# CD2840ADX-V2_1.net
KiCad netlist of a schematic drawn in Altium Designer
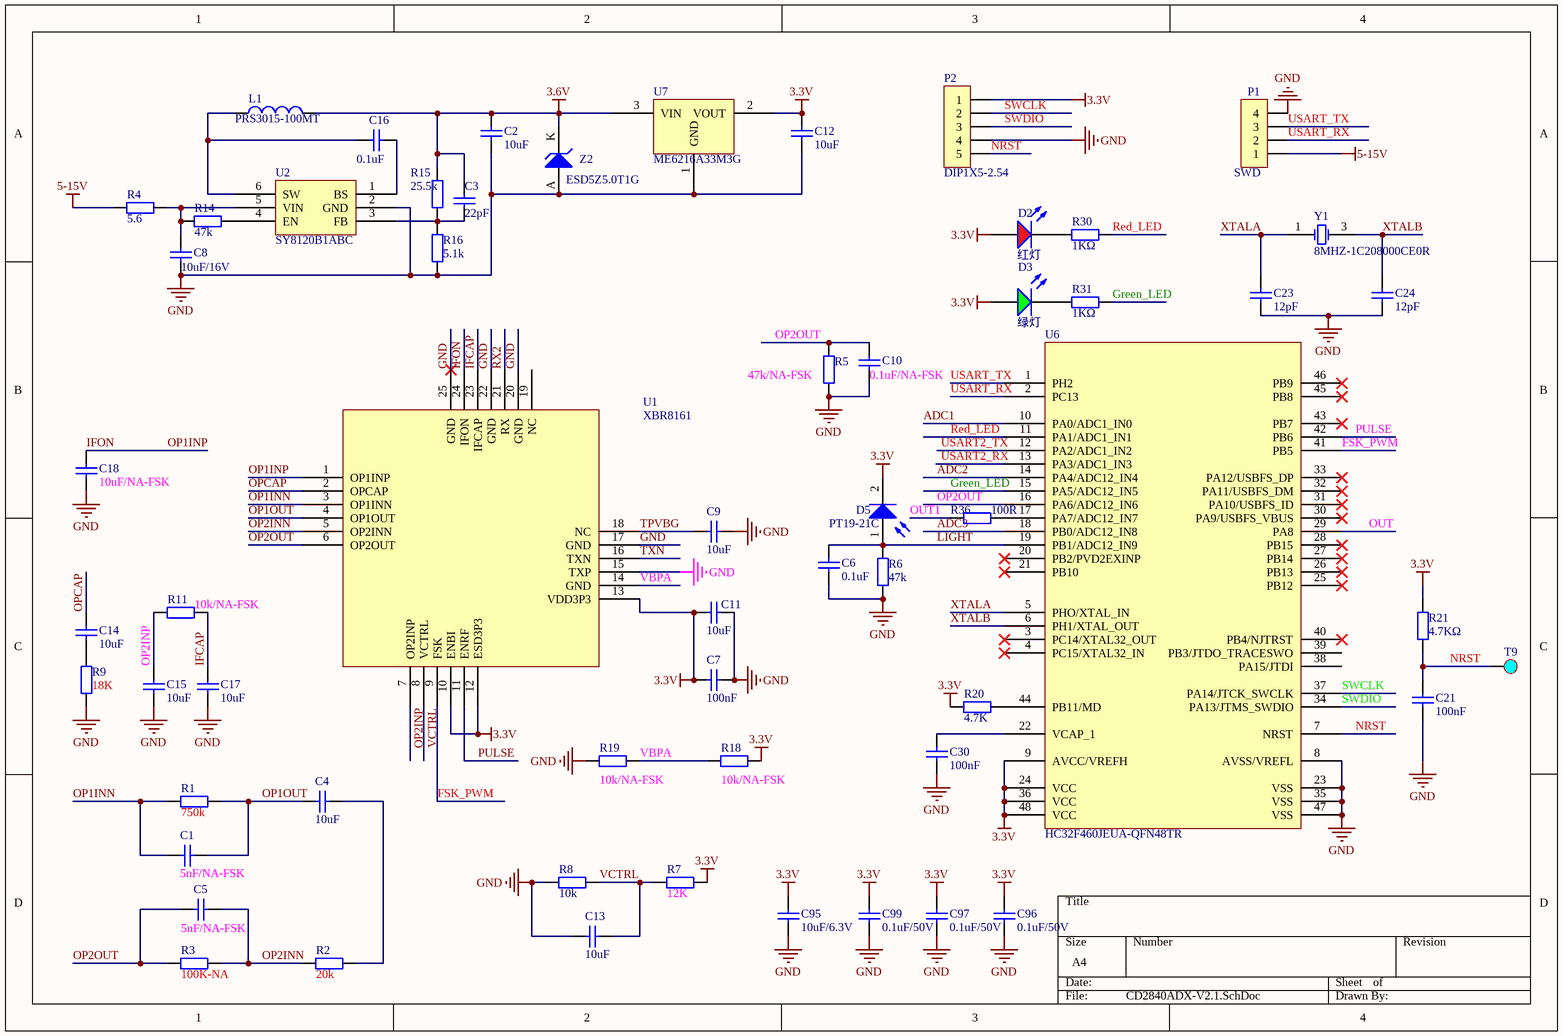
[diagram p0: CD2840ADX-V2.1.SchDoc]

(export (version "E")
  (design (tool "Eeschema 10.0.6"))
  (components
    (comp (ref "C1")
      (value "5nF/NA-FSK")
      (footprint "C0402")
      (description "Capacitor")
      (fields (field (name "PUBLISHER") "Altium Limited"))
      (libsource (lib "Miscellaneous Devices") (part "Cap"))
    )
    (comp (ref "C2")
      (value "10uF")
      (footprint "C0402")
      (description "Capacitor")
      (fields (field (name "PUBLISHER") "Altium Limited"))
      (libsource (lib "Miscellaneous Devices") (part "Cap"))
    )
    (comp (ref "C3")
      (value "22pF")
      (footprint "C0402")
      (description "Capacitor")
      (fields (field (name "PUBLISHER") "Altium Limited"))
      (libsource (lib "Miscellaneous Devices") (part "Cap"))
    )
    (comp (ref "C4")
      (value "10uF")
      (footprint "C0402")
      (description "Capacitor")
      (fields (field (name "PUBLISHER") "Altium Limited"))
      (libsource (lib "Miscellaneous Devices") (part "Cap"))
    )
    (comp (ref "C5")
      (value "5nF/NA-FSK")
      (footprint "C0402")
      (description "Capacitor")
      (fields (field (name "PUBLISHER") "Altium Limited"))
      (libsource (lib "Miscellaneous Devices") (part "Cap"))
    )
    (comp (ref "C6")
      (value "0.1uF")
      (footprint "C0402")
      (description "Capacitor")
      (fields (field (name "PUBLISHER") "Altium Limited"))
      (libsource (lib "Miscellaneous Devices") (part "Cap"))
    )
    (comp (ref "C7")
      (value "100nF")
      (footprint "C0402")
      (description "Capacitor")
      (fields (field (name "PUBLISHER") "Altium Limited"))
      (libsource (lib "Miscellaneous Devices") (part "Cap"))
    )
    (comp (ref "C8")
      (value "10uF/16V")
      (footprint "C0603")
      (description "Capacitor")
      (fields (field (name "PUBLISHER") "Altium Limited"))
      (libsource (lib "Miscellaneous Devices") (part "Cap"))
    )
    (comp (ref "C9")
      (value "10uF")
      (footprint "C0402")
      (description "Capacitor")
      (fields (field (name "PUBLISHER") "Altium Limited"))
      (libsource (lib "Miscellaneous Devices") (part "Cap"))
    )
    (comp (ref "C10")
      (value "0.1uF/NA-FSK")
      (footprint "C0402")
      (description "Capacitor")
      (fields (field (name "PUBLISHER") "Altium Limited"))
      (libsource (lib "Miscellaneous Devices") (part "Cap"))
    )
    (comp (ref "C11")
      (value "10uF")
      (footprint "C0402")
      (description "Capacitor")
      (fields (field (name "PUBLISHER") "Altium Limited"))
      (libsource (lib "Miscellaneous Devices") (part "Cap"))
    )
    (comp (ref "C12")
      (value "10uF")
      (footprint "C0402")
      (description "Capacitor")
      (fields (field (name "PUBLISHER") "Altium Limited"))
      (libsource (lib "Miscellaneous Devices") (part "Cap"))
    )
    (comp (ref "C13")
      (value "10uF")
      (footprint "C0402")
      (description "Capacitor")
      (fields (field (name "PUBLISHER") "Altium Limited"))
      (libsource (lib "Miscellaneous Devices") (part "Cap"))
    )
    (comp (ref "C14")
      (value "10uF")
      (footprint "C0402")
      (description "Capacitor")
      (fields (field (name "PUBLISHER") "Altium Limited"))
      (libsource (lib "Miscellaneous Devices") (part "Cap"))
    )
    (comp (ref "C15")
      (value "10uF")
      (footprint "C0402")
      (description "Capacitor")
      (fields (field (name "PUBLISHER") "Altium Limited"))
      (libsource (lib "Miscellaneous Devices") (part "Cap"))
    )
    (comp (ref "C16")
      (value "0.1uF")
      (footprint "C0402")
      (description "Capacitor")
      (fields (field (name "PUBLISHER") "Altium Limited"))
      (libsource (lib "Miscellaneous Devices") (part "Cap"))
    )
    (comp (ref "C17")
      (value "10uF")
      (footprint "C0402")
      (description "Capacitor")
      (fields (field (name "PUBLISHER") "Altium Limited"))
      (libsource (lib "Miscellaneous Devices") (part "Cap"))
    )
    (comp (ref "C18")
      (value "10uF/NA-FSK")
      (footprint "C0402")
      (description "Capacitor")
      (fields (field (name "PUBLISHER") "Altium Limited"))
      (libsource (lib "Miscellaneous Devices") (part "Cap"))
    )
    (comp (ref "C21")
      (value "100nF")
      (footprint "C0402")
      (description "贴片电容")
      (libsource (lib "Miscellaneous Devices LC") (part "0402 100nF (104) 10% 16V"))
    )
    (comp (ref "C23")
      (value "12pF")
      (footprint "C0402")
      (description "贴片电容")
      (libsource (lib "Cap") (part "0402 22pF (220) 5% 50V"))
    )
    (comp (ref "C24")
      (value "12pF")
      (footprint "C0402")
      (description "贴片电容")
      (libsource (lib "Cap") (part "0402 22pF (220) 5% 50V"))
    )
    (comp (ref "C30")
      (value "100nF")
      (footprint "C0402")
      (description "Capacitor")
      (fields (field (name "PUBLISHER") "Altium Limited"))
      (libsource (lib "Miscellaneous Devices") (part "Cap"))
    )
    (comp (ref "C95")
      (value "10uF/6.3V")
      (footprint "C0402")
      (description "贴片电容")
      (libsource (lib "Cap") (part "0402 2.2nF (222) 10% 50V"))
    )
    (comp (ref "C96")
      (value "0.1uF/50V")
      (footprint "C0402")
      (description "贴片电容")
      (libsource (lib "Cap") (part "0402 2.2nF (222) 10% 50V"))
    )
    (comp (ref "C97")
      (value "0.1uF/50V")
      (footprint "C0402")
      (description "贴片电容")
      (libsource (lib "Cap") (part "0402 2.2nF (222) 10% 50V"))
    )
    (comp (ref "C99")
      (value "0.1uF/50V")
      (footprint "C0402")
      (description "贴片电容")
      (libsource (lib "Cap") (part "0402 2.2nF (222) 10% 50V"))
    )
    (comp (ref "D2")
      (value "红灯")
      (footprint "LC-0603_LED_S1")
      (description "发光二极管")
      (libsource (lib "Miscellaneous Devices LC") (part "0603 红灯"))
    )
    (comp (ref "D3")
      (value "绿灯")
      (footprint "LC-0603_LED_S1")
      (description "发光二极管")
      (libsource (lib "30x35雷达微动底板V0.2") (part "0603 红灯"))
    )
    (comp (ref "D5")
      (value "PT19-21C")
      (footprint "LED-0603")
      (description "Photosensitive Diode")
      (fields (field (name "PUBLISHER") "Altium Limited"))
      (libsource (lib "Miscellaneous Devices") (part "Photo Sen"))
    )
    (comp (ref "L1")
      (value "PRS3015-100MT")
      (footprint "PRS3015")
      (description "Inductor")
      (fields (field (name "PUBLISHER") "Altium Limited"))
      (libsource (lib "Miscellaneous Devices") (part "Inductor"))
    )
    (comp (ref "P1")
      (value "SWD")
      (footprint "XH2.54mm")
      (description "4P接插件")
      (libsource (lib "STM32F407_CORE_BOARD") (part "Header 4"))
    )
    (comp (ref "P2")
      (value "DIP1X5-2.54")
      (footprint "DIP1X5-2.54")
      (description "4P接插件")
      (libsource (lib "CD2840ADX-V2.1") (part "Header 4"))
    )
    (comp (ref "R1")
      (value "750k")
      (footprint "R0402")
      (description "Resistor")
      (fields (field (name "PUBLISHER") "Altium Limited"))
      (libsource (lib "") (part "Res2_2"))
    )
    (comp (ref "R2")
      (value "20k")
      (footprint "R0402")
      (description "Resistor")
      (fields (field (name "PUBLISHER") "Altium Limited"))
      (libsource (lib "") (part "Res2_1"))
    )
    (comp (ref "R3")
      (value "100K-NA")
      (footprint "R0402")
      (description "Resistor")
      (fields (field (name "PUBLISHER") "Altium Limited"))
      (libsource (lib "") (part "Res2_1"))
    )
    (comp (ref "R4")
      (value "5.6")
      (footprint "R0402")
      (description "Resistor")
      (fields (field (name "PUBLISHER") "Altium Limited"))
      (libsource (lib "") (part "Res2_4"))
    )
    (comp (ref "R5")
      (value "47k/NA-FSK")
      (footprint "R0402")
      (description "Resistor")
      (fields (field (name "PUBLISHER") "Altium Limited"))
      (libsource (lib "Miscellaneous Devices") (part "Res2"))
    )
    (comp (ref "R6")
      (value "47k")
      (footprint "R0402")
      (description "Resistor")
      (fields (field (name "PUBLISHER") "Altium Limited"))
      (libsource (lib "Miscellaneous Devices") (part "Res2"))
    )
    (comp (ref "R7")
      (value "12K")
      (footprint "R0402")
      (description "Resistor")
      (fields (field (name "PUBLISHER") "Altium Limited"))
      (libsource (lib "") (part "Res2_1"))
    )
    (comp (ref "R8")
      (value "10k")
      (footprint "R0402")
      (description "Resistor")
      (fields (field (name "PUBLISHER") "Altium Limited"))
      (libsource (lib "") (part "Res2_1"))
    )
    (comp (ref "R9")
      (value "18K")
      (footprint "R0402")
      (description "Resistor")
      (fields (field (name "PUBLISHER") "Altium Limited"))
      (libsource (lib "Miscellaneous Devices") (part "Res2"))
    )
    (comp (ref "R11")
      (value "10k/NA-FSK")
      (footprint "R0402")
      (description "Resistor")
      (fields (field (name "PUBLISHER") "Altium Limited"))
      (libsource (lib "") (part "Res2_1"))
    )
    (comp (ref "R14")
      (value "47k")
      (footprint "R0402")
      (description "Resistor")
      (fields (field (name "PUBLISHER") "Altium Limited"))
      (libsource (lib "") (part "Res2_1"))
    )
    (comp (ref "R15")
      (value "25.5k")
      (footprint "R0402")
      (description "Resistor")
      (fields (field (name "PUBLISHER") "Altium Limited"))
      (libsource (lib "") (part "Res2_3"))
    )
    (comp (ref "R16")
      (value "5.1k")
      (footprint "R0402")
      (description "Resistor")
      (fields (field (name "PUBLISHER") "Altium Limited"))
      (libsource (lib "") (part "Res2_3"))
    )
    (comp (ref "R18")
      (value "10k/NA-FSK")
      (footprint "R0402")
      (description "Resistor")
      (fields (field (name "PUBLISHER") "Altium Limited"))
      (libsource (lib "") (part "Res2_1"))
    )
    (comp (ref "R19")
      (value "10k/NA-FSK")
      (footprint "R0402")
      (description "Resistor")
      (fields (field (name "PUBLISHER") "Altium Limited"))
      (libsource (lib "") (part "Res2_1"))
    )
    (comp (ref "R20")
      (value "4.7K")
      (footprint "R0402")
      (description "Resistor")
      (fields (field (name "PUBLISHER") "Altium Limited"))
      (libsource (lib "") (part "Res2_2"))
    )
    (comp (ref "R21")
      (value "4.7KΩ")
      (footprint "R0402")
      (description "贴片电阻")
      (libsource (lib "Miscellaneous Devices LC") (part "0402 4.7KΩ (4701) 1%"))
    )
    (comp (ref "R30")
      (value "1KΩ")
      (footprint "R0402")
      (description "贴片电阻")
      (libsource (lib "Miscellaneous Devices LC") (part "0402 1KΩ (1001) 1%"))
    )
    (comp (ref "R31")
      (value "1KΩ")
      (footprint "R0402")
      (description "贴片电阻")
      (libsource (lib "Miscellaneous Devices LC") (part "0402 1KΩ (1001) 1%"))
    )
    (comp (ref "R36")
      (value "100R")
      (footprint "R0402")
      (description "贴片电阻")
      (libsource (lib "") (part "0402 4.7KΩ (4701) 1%_1"))
    )
    (comp (ref "T9")
      (value "~")
      (footprint "TestPoints")
      (description "TestPoints")
      (libsource (lib "标准原理图库（特种板）") (part "TestPoints"))
    )
    (comp (ref "U1")
      (value "XBR8161")
      (footprint "QFN24")
      (libsource (lib "altium-import") (part "root_0_XBR8161_"))
    )
    (comp (ref "U2") (value "SY8120B1ABC") (footprint "SOT-23-6") (libsource (lib "Schlib1") (part "H9108")))
    (comp (ref "U6")
      (value "HC32F460JEUA-QFN48TR")
      (footprint "QFN48-5X5mm")
      (libsource (lib "LD-ShouShi-Module-V1.0") (part "HC32F460JETA-LQFP48"))
    )
    (comp (ref "U7")
      (value "ME6216A33M3G")
      (footprint "SOT-23-L")
      (libsource (lib "Schlib1") (part "SSP6206"))
    )
    (comp (ref "Y1")
      (value "8MHZ-1C208000CE0R")
      (footprint "OSC-SMD_3225")
      (description "贴片晶振")
      (libsource (lib "CrystalOscillator") (part "SMD-3225_4P  25MHZ 12PF 10PPM"))
    )
    (comp (ref "Z2")
      (value "ESD5Z5.0T1G")
      (footprint "SOD323")
      (description "Zener Diode")
      (fields (field (name "PUBLISHER") "Altium Limited"))
      (libsource (lib "Miscellaneous Devices") (part "D Zener"))
    )
  )
  (nets
    (net (code "1") (name "/ADC1") (class "Default")
      (node (ref "U6") (pin "10") (pinfunction "PA0/ADC1_IN0_10") (pintype "passive"))
    )
    (net (code "2") (name "/ADC2") (class "Default")
      (node (ref "U6") (pin "14") (pinfunction "PA4/ADC12_IN4_14") (pintype "passive"))
    )
    (net (code "3") (name "/ADC3") (class "Default")
      (node (ref "U6") (pin "18") (pinfunction "PB0/ADC12_IN8_18") (pintype "passive"))
    )
    (net (code "4") (name "/FSK_PWM") (class "Default")
      (node (ref "U1") (pin "9") (pinfunction "FSK_9") (pintype "passive"))
      (node (ref "U6") (pin "41") (pinfunction "PB5_41") (pintype "passive"))
    )
    (net (code "5") (name "/Green_LED") (class "Default")
      (node (ref "R31") (pin "1") (pinfunction "1_1") (pintype "passive"))
      (node (ref "U6") (pin "15") (pinfunction "PA5/ADC12_IN5_15") (pintype "passive"))
    )
    (net (code "6") (name "/IFCAP") (class "Default")
      (node (ref "C17") (pin "2") (pinfunction "2_2") (pintype "passive"))
      (node (ref "R11") (pin "1") (pinfunction "1_1") (pintype "passive"))
      (node (ref "U1") (pin "23") (pinfunction "IFCAP_23") (pintype "passive"))
    )
    (net (code "7") (name "/IFON") (class "Default")
      (node (ref "C18") (pin "2") (pinfunction "2_2") (pintype "passive"))
      (node (ref "U1") (pin "1") (pinfunction "OP1INP_1") (pintype "passive"))
      (node (ref "U1") (pin "24") (pinfunction "IFON_24") (pintype "passive"))
    )
    (net (code "8") (name "/LIGHT") (class "Default")
      (node (ref "C6") (pin "1") (pinfunction "1_1") (pintype "passive"))
      (node (ref "D5") (pin "1") (pinfunction "A_1") (pintype "passive"))
      (node (ref "R6") (pin "1") (pinfunction "1_1") (pintype "passive"))
      (node (ref "U6") (pin "19") (pinfunction "PB1/ADC12_IN9_19") (pintype "passive"))
    )
    (net (code "9") (name "/NRST") (class "Default")
      (node (ref "C21") (pin "2") (pinfunction "2_2") (pintype "passive"))
      (node (ref "P2") (pin "5") (pinfunction "5_5") (pintype "passive"))
      (node (ref "R21") (pin "1") (pinfunction "1_1") (pintype "passive"))
      (node (ref "T9") (pin "1") (pinfunction "1_1") (pintype "passive"))
      (node (ref "U6") (pin "7") (pinfunction "NRST_7") (pintype "passive"))
    )
    (net (code "10") (name "/OP1INN") (class "Default")
      (node (ref "C1") (pin "2") (pinfunction "2_2") (pintype "passive"))
      (node (ref "R1") (pin "1") (pinfunction "1_1") (pintype "passive"))
      (node (ref "U1") (pin "3") (pinfunction "OP1INN_3") (pintype "passive"))
    )
    (net (code "11") (name "/OP1OUT") (class "Default")
      (node (ref "C1") (pin "1") (pinfunction "1_1") (pintype "passive"))
      (node (ref "C4") (pin "2") (pinfunction "2_2") (pintype "passive"))
      (node (ref "R1") (pin "2") (pinfunction "2_2") (pintype "passive"))
      (node (ref "U1") (pin "4") (pinfunction "OP1OUT_4") (pintype "passive"))
    )
    (net (code "12") (name "/OP2INN") (class "Default")
      (node (ref "C5") (pin "2") (pinfunction "2_2") (pintype "passive"))
      (node (ref "R2") (pin "2") (pinfunction "2_2") (pintype "passive"))
      (node (ref "R3") (pin "1") (pinfunction "1_1") (pintype "passive"))
      (node (ref "U1") (pin "5") (pinfunction "OP2INN_5") (pintype "passive"))
    )
    (net (code "13") (name "/OP2INP") (class "Default")
      (node (ref "C15") (pin "1") (pinfunction "1_1") (pintype "passive"))
      (node (ref "R11") (pin "2") (pinfunction "2_2") (pintype "passive"))
      (node (ref "U1") (pin "7") (pinfunction "OP2INP_7") (pintype "passive"))
    )
    (net (code "14") (name "/OP2OUT") (class "Default")
      (node (ref "C10") (pin "1") (pinfunction "1_1") (pintype "passive"))
      (node (ref "C5") (pin "1") (pinfunction "1_1") (pintype "passive"))
      (node (ref "R3") (pin "2") (pinfunction "2_2") (pintype "passive"))
      (node (ref "R5") (pin "1") (pinfunction "1_1") (pintype "passive"))
      (node (ref "U1") (pin "6") (pinfunction "OP2OUT_6") (pintype "passive"))
      (node (ref "U6") (pin "16") (pinfunction "PA6/ADC12_IN6_16") (pintype "passive"))
    )
    (net (code "15") (name "/OPCAP") (class "Default")
      (node (ref "C14") (pin "2") (pinfunction "2_2") (pintype "passive"))
      (node (ref "U1") (pin "2") (pinfunction "OPCAP_2") (pintype "passive"))
    )
    (net (code "16") (name "/OUT") (class "Default")
      (node (ref "U6") (pin "29") (pinfunction "PA8_29") (pintype "passive"))
    )
    (net (code "17") (name "/OUT1") (class "Default")
      (node (ref "R36") (pin "2") (pinfunction "2_2") (pintype "passive"))
    )
    (net (code "18") (name "/PULSE") (class "Default")
      (node (ref "U1") (pin "11") (pinfunction "ENRF_11") (pintype "passive"))
      (node (ref "U6") (pin "42") (pinfunction "PB6_42") (pintype "passive"))
    )
    (net (code "19") (name "/RX2") (class "Default")
      (node (ref "U1") (pin "21") (pinfunction "RX_21") (pintype "passive"))
    )
    (net (code "20") (name "/Red_LED") (class "Default")
      (node (ref "R30") (pin "1") (pinfunction "1_1") (pintype "passive"))
      (node (ref "U6") (pin "11") (pinfunction "PA1/ADC1_IN1_11") (pintype "passive"))
    )
    (net (code "21") (name "/SWCLK") (class "Default")
      (node (ref "P2") (pin "2") (pinfunction "2_2") (pintype "passive"))
      (node (ref "U6") (pin "37") (pinfunction "PA14/JTCK_SWCLK_37") (pintype "passive"))
    )
    (net (code "22") (name "/SWDIO") (class "Default")
      (node (ref "P2") (pin "3") (pinfunction "3_3") (pintype "passive"))
      (node (ref "U6") (pin "34") (pinfunction "PA13/JTMS_SWDIO_34") (pintype "passive"))
    )
    (net (code "23") (name "/TPVBG") (class "Default")
      (node (ref "C9") (pin "2") (pinfunction "2_2") (pintype "passive"))
      (node (ref "U1") (pin "18") (pinfunction "NC_18") (pintype "passive"))
    )
    (net (code "24") (name "/TXN") (class "Default")
      (node (ref "U1") (pin "16") (pinfunction "TXN_16") (pintype "passive"))
    )
    (net (code "25") (name "/USART2_RX") (class "Default")
      (node (ref "U6") (pin "13") (pinfunction "PA3/ADC1_IN3_13") (pintype "passive"))
    )
    (net (code "26") (name "/USART2_TX") (class "Default")
      (node (ref "U6") (pin "12") (pinfunction "PA2/ADC1_IN2_12") (pintype "passive"))
    )
    (net (code "27") (name "/USART_RX") (class "Default")
      (node (ref "P1") (pin "2") (pinfunction "2_2") (pintype "passive"))
      (node (ref "U6") (pin "2") (pinfunction "PC13_2") (pintype "passive"))
    )
    (net (code "28") (name "/USART_TX") (class "Default")
      (node (ref "P1") (pin "3") (pinfunction "3_3") (pintype "passive"))
      (node (ref "U6") (pin "1") (pinfunction "PH2_1") (pintype "passive"))
    )
    (net (code "29") (name "/VBPA") (class "Default")
      (node (ref "R18") (pin "2") (pinfunction "2_2") (pintype "passive"))
      (node (ref "R19") (pin "1") (pinfunction "1_1") (pintype "passive"))
      (node (ref "U1") (pin "14") (pinfunction "GND_14") (pintype "passive"))
    )
    (net (code "30") (name "/VCTRL") (class "Default")
      (node (ref "C13") (pin "1") (pinfunction "1_1") (pintype "passive"))
      (node (ref "R7") (pin "2") (pinfunction "2_2") (pintype "passive"))
      (node (ref "R8") (pin "1") (pinfunction "1_1") (pintype "passive"))
      (node (ref "U1") (pin "8") (pinfunction "VCTRL_8") (pintype "passive"))
    )
    (net (code "31") (name "/XTALA") (class "Default")
      (node (ref "C23") (pin "2") (pinfunction "2_2") (pintype "passive"))
      (node (ref "U6") (pin "5") (pinfunction "PHO/XTAL_IN_5") (pintype "passive"))
      (node (ref "Y1") (pin "1") (pinfunction "OSC1_1") (pintype "passive"))
    )
    (net (code "32") (name "/XTALB") (class "Default")
      (node (ref "C24") (pin "2") (pinfunction "2_2") (pintype "passive"))
      (node (ref "U6") (pin "6") (pinfunction "PH1/XTAL_OUT_6") (pintype "passive"))
      (node (ref "Y1") (pin "3") (pinfunction "OSC2_3") (pintype "passive"))
    )
    (net (code "33") (name "3.3V") (class "Default")
      (node (ref "C11") (pin "2") (pinfunction "2_2") (pintype "passive"))
      (node (ref "C12") (pin "1") (pinfunction "1_1") (pintype "passive"))
      (node (ref "C7") (pin "2") (pinfunction "2_2") (pintype "passive"))
      (node (ref "C95") (pin "1") (pinfunction "1_1") (pintype "passive"))
      (node (ref "C96") (pin "1") (pinfunction "1_1") (pintype "passive"))
      (node (ref "C97") (pin "1") (pinfunction "1_1") (pintype "passive"))
      (node (ref "C99") (pin "1") (pinfunction "1_1") (pintype "passive"))
      (node (ref "D2") (pin "A") (pinfunction "A_A") (pintype "passive"))
      (node (ref "D3") (pin "A") (pinfunction "A_A") (pintype "passive"))
      (node (ref "D5") (pin "2") (pinfunction "K_2") (pintype "passive"))
      (node (ref "P2") (pin "1") (pinfunction "1_1") (pintype "passive"))
      (node (ref "R18") (pin "1") (pinfunction "1_1") (pintype "passive"))
      (node (ref "R20") (pin "1") (pinfunction "1_1") (pintype "passive"))
      (node (ref "R21") (pin "2") (pinfunction "2_2") (pintype "passive"))
      (node (ref "R7") (pin "1") (pinfunction "1_1") (pintype "passive"))
      (node (ref "U1") (pin "10") (pinfunction "ENBI_10") (pintype "passive"))
      (node (ref "U1") (pin "12") (pinfunction "ESD3P3_12") (pintype "passive"))
      (node (ref "U1") (pin "13") (pinfunction "VDD3P3_13") (pintype "passive"))
      (node (ref "U6") (pin "24") (pinfunction "VCC_24") (pintype "passive"))
      (node (ref "U6") (pin "36") (pinfunction "VCC_36") (pintype "passive"))
      (node (ref "U6") (pin "48") (pinfunction "VCC_48") (pintype "passive"))
      (node (ref "U6") (pin "9") (pinfunction "AVCC/VREFH_9") (pintype "passive"))
      (node (ref "U7") (pin "2") (pinfunction "VOUT_2") (pintype "passive"))
    )
    (net (code "34") (name "3.6V") (class "Default")
      (node (ref "C2") (pin "1") (pinfunction "1_1") (pintype "passive"))
      (node (ref "C3") (pin "2") (pinfunction "2_2") (pintype "passive"))
      (node (ref "L1") (pin "2") (pinfunction "2_2") (pintype "passive"))
      (node (ref "R15") (pin "2") (pinfunction "2_2") (pintype "passive"))
      (node (ref "U7") (pin "3") (pinfunction "VIN_3") (pintype "passive"))
      (node (ref "Z2") (pin "K") (pinfunction "K_K") (pintype "passive"))
    )
    (net (code "35") (name "5-15V") (class "Default")
      (node (ref "P1") (pin "1") (pinfunction "1_1") (pintype "passive"))
      (node (ref "R4") (pin "1") (pinfunction "1_1") (pintype "passive"))
    )
    (net (code "36") (name "GND") (class "Default")
      (node (ref "C10") (pin "2") (pinfunction "2_2") (pintype "passive"))
      (node (ref "C11") (pin "1") (pinfunction "1_1") (pintype "passive"))
      (node (ref "C12") (pin "2") (pinfunction "2_2") (pintype "passive"))
      (node (ref "C13") (pin "2") (pinfunction "2_2") (pintype "passive"))
      (node (ref "C15") (pin "2") (pinfunction "2_2") (pintype "passive"))
      (node (ref "C17") (pin "1") (pinfunction "1_1") (pintype "passive"))
      (node (ref "C18") (pin "1") (pinfunction "1_1") (pintype "passive"))
      (node (ref "C2") (pin "2") (pinfunction "2_2") (pintype "passive"))
      (node (ref "C21") (pin "1") (pinfunction "1_1") (pintype "passive"))
      (node (ref "C23") (pin "1") (pinfunction "1_1") (pintype "passive"))
      (node (ref "C24") (pin "1") (pinfunction "1_1") (pintype "passive"))
      (node (ref "C30") (pin "2") (pinfunction "2_2") (pintype "passive"))
      (node (ref "C6") (pin "2") (pinfunction "2_2") (pintype "passive"))
      (node (ref "C7") (pin "1") (pinfunction "1_1") (pintype "passive"))
      (node (ref "C8") (pin "2") (pinfunction "2_2") (pintype "passive"))
      (node (ref "C9") (pin "1") (pinfunction "1_1") (pintype "passive"))
      (node (ref "C95") (pin "2") (pinfunction "2_2") (pintype "passive"))
      (node (ref "C96") (pin "2") (pinfunction "2_2") (pintype "passive"))
      (node (ref "C97") (pin "2") (pinfunction "2_2") (pintype "passive"))
      (node (ref "C99") (pin "2") (pinfunction "2_2") (pintype "passive"))
      (node (ref "P1") (pin "4") (pinfunction "4_4") (pintype "passive"))
      (node (ref "P2") (pin "4") (pinfunction "4_4") (pintype "passive"))
      (node (ref "R16") (pin "1") (pinfunction "1_1") (pintype "passive"))
      (node (ref "R19") (pin "2") (pinfunction "2_2") (pintype "passive"))
      (node (ref "R5") (pin "2") (pinfunction "2_2") (pintype "passive"))
      (node (ref "R6") (pin "2") (pinfunction "2_2") (pintype "passive"))
      (node (ref "R8") (pin "2") (pinfunction "2_2") (pintype "passive"))
      (node (ref "R9") (pin "2") (pinfunction "2_2") (pintype "passive"))
      (node (ref "U1") (pin "15") (pinfunction "TXP_15") (pintype "passive"))
      (node (ref "U1") (pin "17") (pinfunction "GND_17") (pintype "passive"))
      (node (ref "U1") (pin "20") (pinfunction "GND_20") (pintype "passive"))
      (node (ref "U1") (pin "22") (pinfunction "GND_22") (pintype "passive"))
      (node (ref "U1") (pin "25") (pinfunction "GND_25") (pintype "passive"))
      (node (ref "U2") (pin "2") (pinfunction "GND_2") (pintype "passive"))
      (node (ref "U6") (pin "23") (pinfunction "VSS_23") (pintype "passive"))
      (node (ref "U6") (pin "35") (pinfunction "VSS_35") (pintype "passive"))
      (node (ref "U6") (pin "47") (pinfunction "VSS_47") (pintype "passive"))
      (node (ref "U6") (pin "8") (pinfunction "AVSS/VREFL_8") (pintype "passive"))
      (node (ref "U7") (pin "1") (pinfunction "GND_1") (pintype "passive"))
      (node (ref "Z2") (pin "A") (pinfunction "A_A") (pintype "passive"))
    )
    (net (code "37") (name "Net-(C4-Pad1)") (class "Default")
      (node (ref "C4") (pin "1") (pinfunction "1_1") (pintype "passive"))
      (node (ref "R2") (pin "1") (pinfunction "1_1") (pintype "passive"))
    )
    (net (code "38") (name "Net-(C14-Pad1)") (class "Default")
      (node (ref "C14") (pin "1") (pinfunction "1_1") (pintype "passive"))
      (node (ref "R9") (pin "1") (pinfunction "1_1") (pintype "passive"))
    )
    (net (code "39") (name "Net-(D2-PadK)") (class "Default")
      (node (ref "D2") (pin "K") (pinfunction "K_K") (pintype "passive"))
      (node (ref "R30") (pin "2") (pinfunction "2_2") (pintype "passive"))
    )
    (net (code "40") (name "Net-(D3-PadK)") (class "Default")
      (node (ref "D3") (pin "K") (pinfunction "K_K") (pintype "passive"))
      (node (ref "R31") (pin "2") (pinfunction "2_2") (pintype "passive"))
    )
    (net (code "41") (name "Net-(U2-BS)") (class "Default")
      (node (ref "C16") (pin "2") (pinfunction "2_2") (pintype "passive"))
      (node (ref "U2") (pin "1") (pinfunction "BS_1") (pintype "passive"))
    )
    (net (code "42") (name "Net-(U2-EN)") (class "Default")
      (node (ref "R14") (pin "1") (pinfunction "1_1") (pintype "passive"))
      (node (ref "U2") (pin "4") (pinfunction "EN_4") (pintype "passive"))
    )
    (net (code "43") (name "Net-(U2-FB)") (class "Default")
      (node (ref "C3") (pin "1") (pinfunction "1_1") (pintype "passive"))
      (node (ref "R15") (pin "1") (pinfunction "1_1") (pintype "passive"))
      (node (ref "R16") (pin "2") (pinfunction "2_2") (pintype "passive"))
      (node (ref "U2") (pin "3") (pinfunction "FB_3") (pintype "passive"))
    )
    (net (code "44") (name "Net-(U2-SW)") (class "Default")
      (node (ref "C16") (pin "1") (pinfunction "1_1") (pintype "passive"))
      (node (ref "L1") (pin "1") (pinfunction "1_1") (pintype "passive"))
      (node (ref "U2") (pin "6") (pinfunction "SW_6") (pintype "passive"))
    )
    (net (code "45") (name "Net-(U2-VIN)") (class "Default")
      (node (ref "C8") (pin "1") (pinfunction "1_1") (pintype "passive"))
      (node (ref "R14") (pin "2") (pinfunction "2_2") (pintype "passive"))
      (node (ref "R4") (pin "2") (pinfunction "2_2") (pintype "passive"))
      (node (ref "U2") (pin "5") (pinfunction "VIN_5") (pintype "passive"))
    )
    (net (code "46") (name "Net-(U6-PA7{slash}ADC12_IN7)") (class "Default")
      (node (ref "R36") (pin "1") (pinfunction "1_1") (pintype "passive"))
      (node (ref "U6") (pin "17") (pinfunction "PA7/ADC12_IN7_17") (pintype "passive"))
    )
    (net (code "47") (name "Net-(U6-PB11{slash}MD)") (class "Default")
      (node (ref "R20") (pin "2") (pinfunction "2_2") (pintype "passive"))
      (node (ref "U6") (pin "44") (pinfunction "PB11/MD_44") (pintype "passive"))
    )
    (net (code "48") (name "Net-(U6-VCAP_1)") (class "Default")
      (node (ref "C30") (pin "1") (pinfunction "1_1") (pintype "passive"))
      (node (ref "U6") (pin "22") (pinfunction "VCAP_1_22") (pintype "passive"))
    )
    (net (code "49") (name "unconnected-(U1-NC-Pad19)") (class "Default")
      (node (ref "U1") (pin "19") (pinfunction "NC_19") (pintype "passive"))
    )
    (net (code "50") (name "unconnected-(U6-PA9{slash}USBFS_VBUS-Pad30)") (class "Default")
      (node (ref "U6") (pin "30") (pinfunction "PA9/USBFS_VBUS_30") (pintype "passive+no_connect"))
    )
    (net (code "51") (name "unconnected-(U6-PA10{slash}USBFS_ID-Pad31)") (class "Default")
      (node (ref "U6") (pin "31") (pinfunction "PA10/USBFS_ID_31") (pintype "passive+no_connect"))
    )
    (net (code "52") (name "unconnected-(U6-PA11{slash}USBFS_DM-Pad32)") (class "Default")
      (node (ref "U6") (pin "32") (pinfunction "PA11/USBFS_DM_32") (pintype "passive+no_connect"))
    )
    (net (code "53") (name "unconnected-(U6-PA12{slash}USBFS_DP-Pad33)") (class "Default")
      (node (ref "U6") (pin "33") (pinfunction "PA12/USBFS_DP_33") (pintype "passive+no_connect"))
    )
    (net (code "54") (name "unconnected-(U6-PA15{slash}JTDI-Pad38)") (class "Default")
      (node (ref "U6") (pin "38") (pinfunction "PA15/JTDI_38") (pintype "passive"))
    )
    (net (code "55") (name "unconnected-(U6-PB2{slash}PVD2EXINP-Pad20)") (class "Default")
      (node (ref "U6") (pin "20") (pinfunction "PB2/PVD2EXINP_20") (pintype "passive+no_connect"))
    )
    (net (code "56") (name "unconnected-(U6-PB3{slash}JTDO_TRACESWO-Pad39)") (class "Default")
      (node (ref "U6") (pin "39") (pinfunction "PB3/JTDO_TRACESWO_39") (pintype "passive"))
    )
    (net (code "57") (name "unconnected-(U6-PB4{slash}NJTRST-Pad40)") (class "Default")
      (node (ref "U6") (pin "40") (pinfunction "PB4/NJTRST_40") (pintype "passive+no_connect"))
    )
    (net (code "58") (name "unconnected-(U6-PB7-Pad43)") (class "Default")
      (node (ref "U6") (pin "43") (pinfunction "PB7_43") (pintype "passive+no_connect"))
    )
    (net (code "59") (name "unconnected-(U6-PB8-Pad45)") (class "Default")
      (node (ref "U6") (pin "45") (pinfunction "PB8_45") (pintype "passive+no_connect"))
    )
    (net (code "60") (name "unconnected-(U6-PB9-Pad46)") (class "Default")
      (node (ref "U6") (pin "46") (pinfunction "PB9_46") (pintype "passive+no_connect"))
    )
    (net (code "61") (name "unconnected-(U6-PB10-Pad21)") (class "Default")
      (node (ref "U6") (pin "21") (pinfunction "PB10_21") (pintype "passive+no_connect"))
    )
    (net (code "62") (name "unconnected-(U6-PB12-Pad25)") (class "Default")
      (node (ref "U6") (pin "25") (pinfunction "PB12_25") (pintype "passive+no_connect"))
    )
    (net (code "63") (name "unconnected-(U6-PB13-Pad26)") (class "Default")
      (node (ref "U6") (pin "26") (pinfunction "PB13_26") (pintype "passive+no_connect"))
    )
    (net (code "64") (name "unconnected-(U6-PB14-Pad27)") (class "Default")
      (node (ref "U6") (pin "27") (pinfunction "PB14_27") (pintype "passive+no_connect"))
    )
    (net (code "65") (name "unconnected-(U6-PB15-Pad28)") (class "Default")
      (node (ref "U6") (pin "28") (pinfunction "PB15_28") (pintype "passive+no_connect"))
    )
    (net (code "66") (name "unconnected-(U6-PC14{slash}XTAL32_OUT-Pad3)") (class "Default")
      (node (ref "U6") (pin "3") (pinfunction "PC14/XTAL32_OUT_3") (pintype "passive+no_connect"))
    )
    (net (code "67") (name "unconnected-(U6-PC15{slash}XTAL32_IN-Pad4)") (class "Default")
      (node (ref "U6") (pin "4") (pinfunction "PC15/XTAL32_IN_4") (pintype "passive+no_connect"))
    )
  )
)
